# untitled.net
KiCad netlist of a schematic drawn in EAGLE
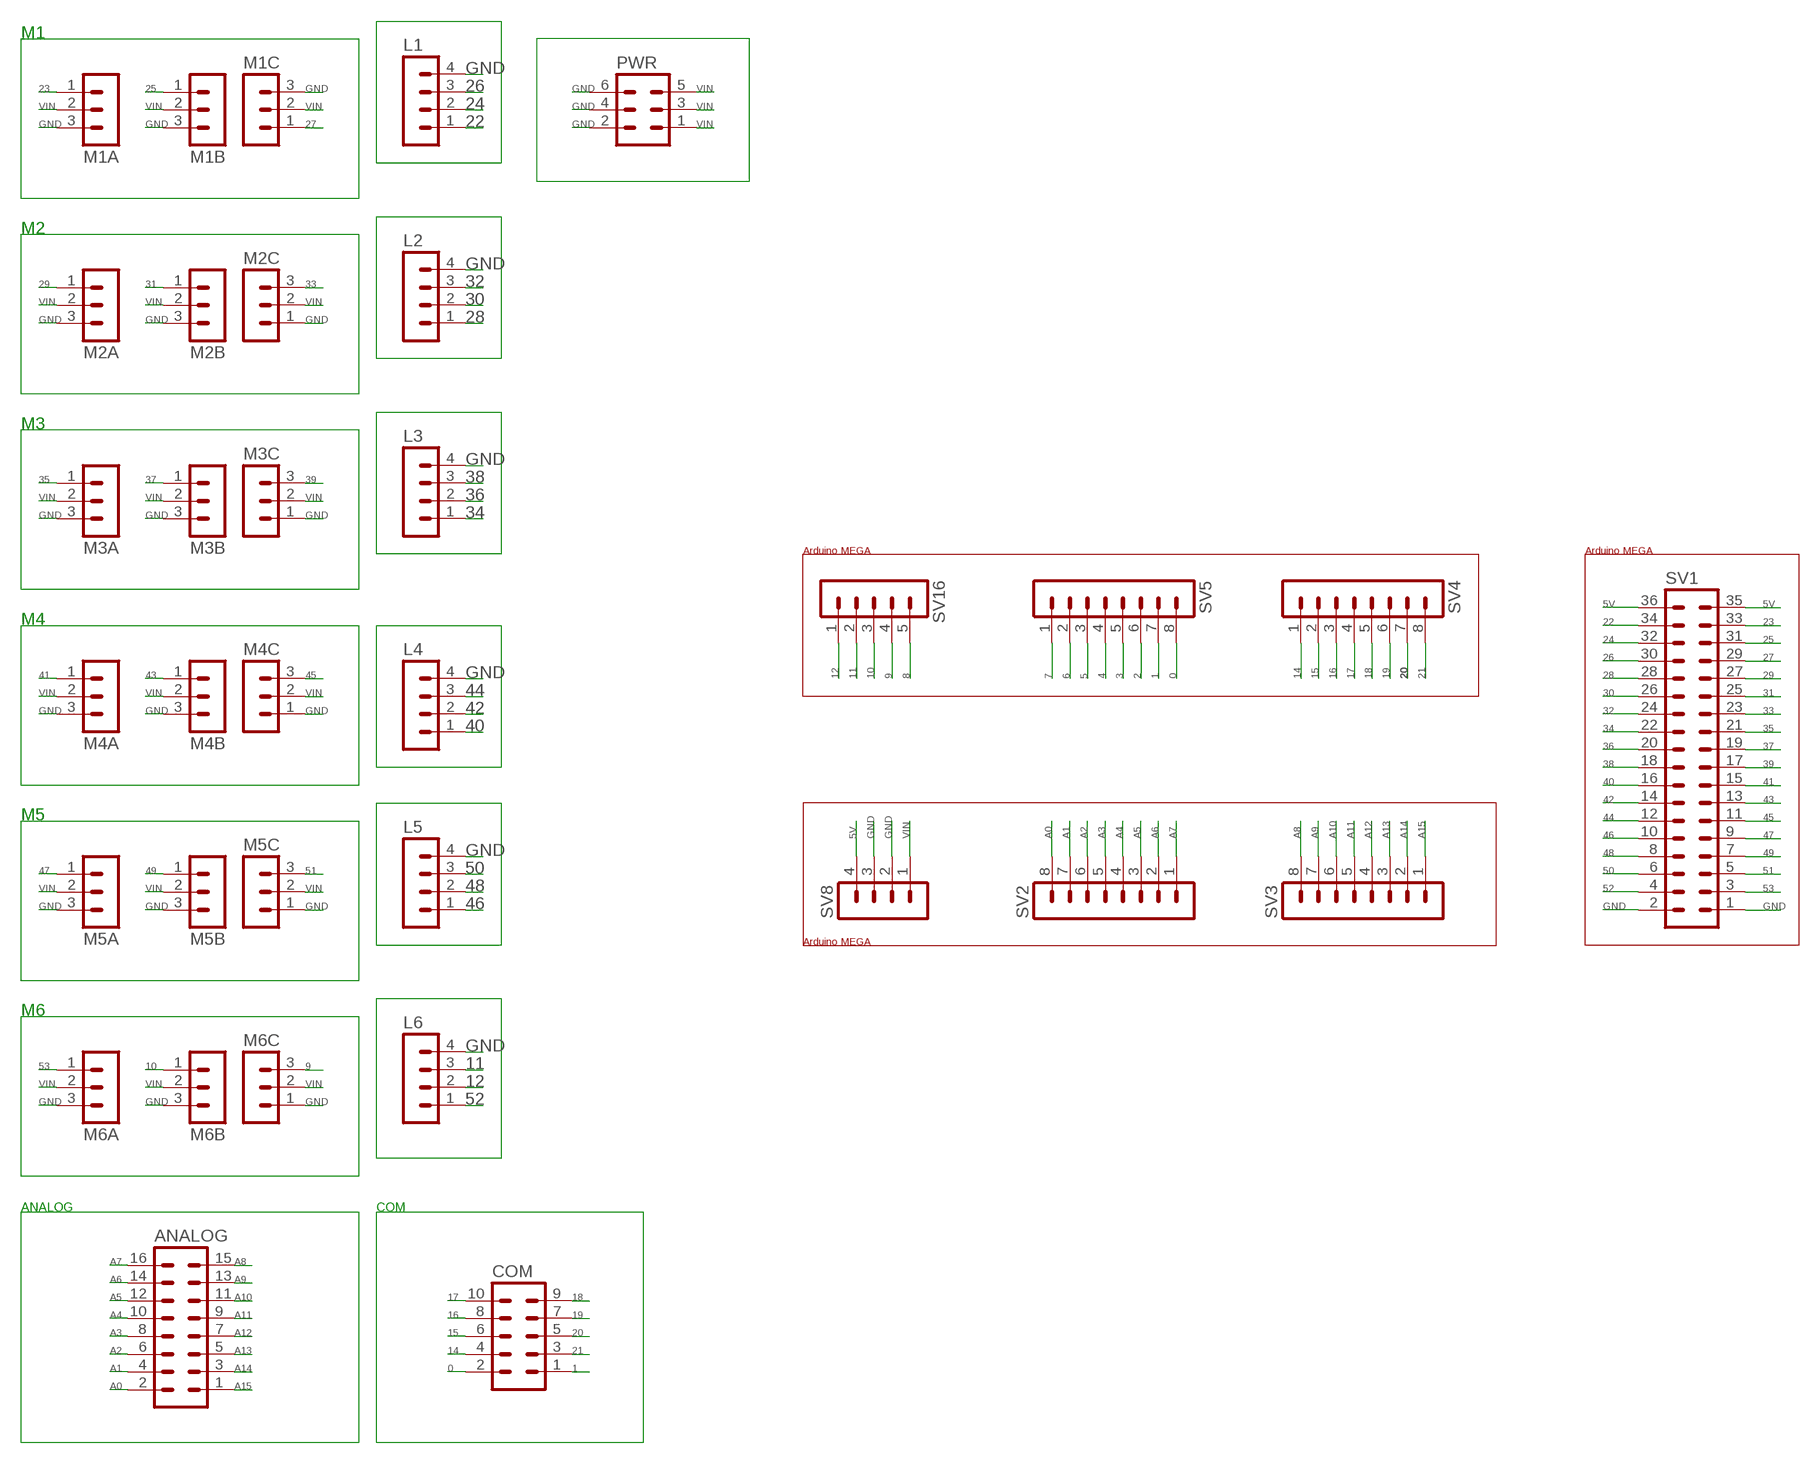
[diagram p0: schematic, sheet 1]

(export (version "E")
  (design (tool "Eeschema 10.0.6"))
  (components
    (comp (ref "ANALOG")
      (value "MA08-2")
      (footprint "eagle-import:MA08-2")
      (libsource (lib "eagle-import") (part "MA08-2"))
    )
    (comp (ref "COM")
      (value "MA05-2")
      (footprint "eagle-import:MA05-2")
      (libsource (lib "eagle-import") (part "MA05-2"))
    )
    (comp (ref "L1")
      (value "MA04-1")
      (footprint "eagle-import:MA04-1")
      (libsource (lib "eagle-import") (part "MA04-1"))
    )
    (comp (ref "L2")
      (value "MA04-1")
      (footprint "eagle-import:MA04-1")
      (libsource (lib "eagle-import") (part "MA04-1"))
    )
    (comp (ref "L3")
      (value "MA04-1")
      (footprint "eagle-import:MA04-1")
      (libsource (lib "eagle-import") (part "MA04-1"))
    )
    (comp (ref "L4")
      (value "MA04-1")
      (footprint "eagle-import:MA04-1")
      (libsource (lib "eagle-import") (part "MA04-1"))
    )
    (comp (ref "L5")
      (value "MA04-1")
      (footprint "eagle-import:MA04-1")
      (libsource (lib "eagle-import") (part "MA04-1"))
    )
    (comp (ref "L6")
      (value "MA04-1")
      (footprint "eagle-import:MA04-1")
      (libsource (lib "eagle-import") (part "MA04-1"))
    )
    (comp (ref "M1A")
      (value "MA03-1")
      (footprint "eagle-import:MA03-1")
      (libsource (lib "eagle-import") (part "MA03-1"))
    )
    (comp (ref "M1B")
      (value "MA03-1")
      (footprint "eagle-import:MA03-1")
      (libsource (lib "eagle-import") (part "MA03-1"))
    )
    (comp (ref "M1C")
      (value "MA03-1")
      (footprint "eagle-import:MA03-1")
      (libsource (lib "eagle-import") (part "MA03-1"))
    )
    (comp (ref "M2A")
      (value "MA03-1")
      (footprint "eagle-import:MA03-1")
      (libsource (lib "eagle-import") (part "MA03-1"))
    )
    (comp (ref "M2B")
      (value "MA03-1")
      (footprint "eagle-import:MA03-1")
      (libsource (lib "eagle-import") (part "MA03-1"))
    )
    (comp (ref "M2C")
      (value "MA03-1")
      (footprint "eagle-import:MA03-1")
      (libsource (lib "eagle-import") (part "MA03-1"))
    )
    (comp (ref "M3A")
      (value "MA03-1")
      (footprint "eagle-import:MA03-1")
      (libsource (lib "eagle-import") (part "MA03-1"))
    )
    (comp (ref "M3B")
      (value "MA03-1")
      (footprint "eagle-import:MA03-1")
      (libsource (lib "eagle-import") (part "MA03-1"))
    )
    (comp (ref "M3C")
      (value "MA03-1")
      (footprint "eagle-import:MA03-1")
      (libsource (lib "eagle-import") (part "MA03-1"))
    )
    (comp (ref "M4A")
      (value "MA03-1")
      (footprint "eagle-import:MA03-1")
      (libsource (lib "eagle-import") (part "MA03-1"))
    )
    (comp (ref "M4B")
      (value "MA03-1")
      (footprint "eagle-import:MA03-1")
      (libsource (lib "eagle-import") (part "MA03-1"))
    )
    (comp (ref "M4C")
      (value "MA03-1")
      (footprint "eagle-import:MA03-1")
      (libsource (lib "eagle-import") (part "MA03-1"))
    )
    (comp (ref "M5A")
      (value "MA03-1")
      (footprint "eagle-import:MA03-1")
      (libsource (lib "eagle-import") (part "MA03-1"))
    )
    (comp (ref "M5B")
      (value "MA03-1")
      (footprint "eagle-import:MA03-1")
      (libsource (lib "eagle-import") (part "MA03-1"))
    )
    (comp (ref "M5C")
      (value "MA03-1")
      (footprint "eagle-import:MA03-1")
      (libsource (lib "eagle-import") (part "MA03-1"))
    )
    (comp (ref "M6A")
      (value "MA03-1")
      (footprint "eagle-import:MA03-1")
      (libsource (lib "eagle-import") (part "MA03-1"))
    )
    (comp (ref "M6B")
      (value "MA03-1")
      (footprint "eagle-import:MA03-1")
      (libsource (lib "eagle-import") (part "MA03-1"))
    )
    (comp (ref "M6C")
      (value "MA03-1")
      (footprint "eagle-import:MA03-1")
      (libsource (lib "eagle-import") (part "MA03-1"))
    )
    (comp (ref "PWR")
      (value "MA03-2")
      (footprint "eagle-import:MA03-2")
      (libsource (lib "eagle-import") (part "MA03-2"))
    )
    (comp (ref "SV1")
      (value "MA18-2")
      (footprint "eagle-import:MA18-2")
      (libsource (lib "eagle-import") (part "MA18-2"))
    )
    (comp (ref "SV2")
      (value "MA08-1")
      (footprint "eagle-import:MA08-1")
      (libsource (lib "eagle-import") (part "MA08-1"))
    )
    (comp (ref "SV3")
      (value "MA08-1")
      (footprint "eagle-import:MA08-1")
      (libsource (lib "eagle-import") (part "MA08-1"))
    )
    (comp (ref "SV4")
      (value "MA08-1")
      (footprint "eagle-import:MA08-1")
      (libsource (lib "eagle-import") (part "MA08-1"))
    )
    (comp (ref "SV5")
      (value "MA08-1")
      (footprint "eagle-import:MA08-1")
      (libsource (lib "eagle-import") (part "MA08-1"))
    )
    (comp (ref "SV8")
      (value "MA04-1")
      (footprint "eagle-import:MA04-1")
      (libsource (lib "eagle-import") (part "MA04-1"))
    )
    (comp (ref "SV16")
      (value "MA05-1")
      (footprint "eagle-import:MA05-1")
      (libsource (lib "eagle-import") (part "MA05-1"))
    )
  )
  (nets
    (net (code "1") (name "/0") (class "Default")
      (node (ref "COM") (pin "2") (pinfunction "2_2") (pintype "passive"))
      (node (ref "SV5") (pin "8") (pinfunction "8_8") (pintype "passive"))
    )
    (net (code "2") (name "/1") (class "Default")
      (node (ref "COM") (pin "1") (pinfunction "1_1") (pintype "passive"))
      (node (ref "SV5") (pin "7") (pinfunction "7_7") (pintype "passive"))
    )
    (net (code "3") (name "/2") (class "Default")
      (node (ref "SV5") (pin "6") (pinfunction "6_6") (pintype "passive"))
    )
    (net (code "4") (name "/3") (class "Default")
      (node (ref "SV5") (pin "5") (pinfunction "5_5") (pintype "passive"))
    )
    (net (code "5") (name "/4") (class "Default")
      (node (ref "SV5") (pin "4") (pinfunction "4_4") (pintype "passive"))
    )
    (net (code "6") (name "/5") (class "Default")
      (node (ref "SV5") (pin "3") (pinfunction "3_3") (pintype "passive"))
    )
    (net (code "7") (name "/5V") (class "Default")
      (node (ref "SV1") (pin "35") (pinfunction "35_35") (pintype "passive"))
      (node (ref "SV1") (pin "36") (pinfunction "36_36") (pintype "passive"))
      (node (ref "SV8") (pin "4") (pinfunction "4_4") (pintype "passive"))
    )
    (net (code "8") (name "/6") (class "Default")
      (node (ref "SV5") (pin "2") (pinfunction "2_2") (pintype "passive"))
    )
    (net (code "9") (name "/7") (class "Default")
      (node (ref "SV5") (pin "1") (pinfunction "1_1") (pintype "passive"))
    )
    (net (code "10") (name "/8") (class "Default")
      (node (ref "SV16") (pin "5") (pinfunction "5_5") (pintype "passive"))
    )
    (net (code "11") (name "/9") (class "Default")
      (node (ref "M6C") (pin "3") (pinfunction "3_3") (pintype "passive"))
      (node (ref "SV16") (pin "4") (pinfunction "4_4") (pintype "passive"))
    )
    (net (code "12") (name "/10") (class "Default")
      (node (ref "M6B") (pin "1") (pinfunction "1_1") (pintype "passive"))
      (node (ref "SV16") (pin "3") (pinfunction "3_3") (pintype "passive"))
    )
    (net (code "13") (name "/11") (class "Default")
      (node (ref "L6") (pin "3") (pinfunction "3_3") (pintype "passive"))
      (node (ref "SV16") (pin "2") (pinfunction "2_2") (pintype "passive"))
    )
    (net (code "14") (name "/12") (class "Default")
      (node (ref "L6") (pin "2") (pinfunction "2_2") (pintype "passive"))
      (node (ref "SV16") (pin "1") (pinfunction "1_1") (pintype "passive"))
    )
    (net (code "15") (name "/14") (class "Default")
      (node (ref "COM") (pin "4") (pinfunction "4_4") (pintype "passive"))
      (node (ref "SV4") (pin "1") (pinfunction "1_1") (pintype "passive"))
    )
    (net (code "16") (name "/15") (class "Default")
      (node (ref "COM") (pin "6") (pinfunction "6_6") (pintype "passive"))
      (node (ref "SV4") (pin "2") (pinfunction "2_2") (pintype "passive"))
    )
    (net (code "17") (name "/16") (class "Default")
      (node (ref "COM") (pin "8") (pinfunction "8_8") (pintype "passive"))
      (node (ref "SV4") (pin "3") (pinfunction "3_3") (pintype "passive"))
    )
    (net (code "18") (name "/17") (class "Default")
      (node (ref "COM") (pin "10") (pinfunction "10_10") (pintype "passive"))
      (node (ref "SV4") (pin "4") (pinfunction "4_4") (pintype "passive"))
    )
    (net (code "19") (name "/18") (class "Default")
      (node (ref "COM") (pin "9") (pinfunction "9_9") (pintype "passive"))
      (node (ref "SV4") (pin "5") (pinfunction "5_5") (pintype "passive"))
    )
    (net (code "20") (name "/19") (class "Default")
      (node (ref "COM") (pin "7") (pinfunction "7_7") (pintype "passive"))
      (node (ref "SV4") (pin "6") (pinfunction "6_6") (pintype "passive"))
    )
    (net (code "21") (name "/20") (class "Default")
      (node (ref "COM") (pin "5") (pinfunction "5_5") (pintype "passive"))
      (node (ref "SV4") (pin "7") (pinfunction "7_7") (pintype "passive"))
    )
    (net (code "22") (name "/21") (class "Default")
      (node (ref "COM") (pin "3") (pinfunction "3_3") (pintype "passive"))
      (node (ref "SV4") (pin "8") (pinfunction "8_8") (pintype "passive"))
    )
    (net (code "23") (name "/22") (class "Default")
      (node (ref "L1") (pin "1") (pinfunction "1_1") (pintype "passive"))
      (node (ref "SV1") (pin "34") (pinfunction "34_34") (pintype "passive"))
    )
    (net (code "24") (name "/23") (class "Default")
      (node (ref "M1A") (pin "1") (pinfunction "1_1") (pintype "passive"))
      (node (ref "SV1") (pin "33") (pinfunction "33_33") (pintype "passive"))
    )
    (net (code "25") (name "/24") (class "Default")
      (node (ref "L1") (pin "2") (pinfunction "2_2") (pintype "passive"))
      (node (ref "SV1") (pin "32") (pinfunction "32_32") (pintype "passive"))
    )
    (net (code "26") (name "/25") (class "Default")
      (node (ref "M1B") (pin "1") (pinfunction "1_1") (pintype "passive"))
      (node (ref "SV1") (pin "31") (pinfunction "31_31") (pintype "passive"))
    )
    (net (code "27") (name "/26") (class "Default")
      (node (ref "L1") (pin "3") (pinfunction "3_3") (pintype "passive"))
      (node (ref "SV1") (pin "30") (pinfunction "30_30") (pintype "passive"))
    )
    (net (code "28") (name "/27") (class "Default")
      (node (ref "M1C") (pin "1") (pinfunction "1_1") (pintype "passive"))
      (node (ref "SV1") (pin "29") (pinfunction "29_29") (pintype "passive"))
    )
    (net (code "29") (name "/28") (class "Default")
      (node (ref "L2") (pin "1") (pinfunction "1_1") (pintype "passive"))
      (node (ref "SV1") (pin "28") (pinfunction "28_28") (pintype "passive"))
    )
    (net (code "30") (name "/29") (class "Default")
      (node (ref "M2A") (pin "1") (pinfunction "1_1") (pintype "passive"))
      (node (ref "SV1") (pin "27") (pinfunction "27_27") (pintype "passive"))
    )
    (net (code "31") (name "/30") (class "Default")
      (node (ref "L2") (pin "2") (pinfunction "2_2") (pintype "passive"))
      (node (ref "SV1") (pin "26") (pinfunction "26_26") (pintype "passive"))
    )
    (net (code "32") (name "/31") (class "Default")
      (node (ref "M2B") (pin "1") (pinfunction "1_1") (pintype "passive"))
      (node (ref "SV1") (pin "25") (pinfunction "25_25") (pintype "passive"))
    )
    (net (code "33") (name "/32") (class "Default")
      (node (ref "L2") (pin "3") (pinfunction "3_3") (pintype "passive"))
      (node (ref "SV1") (pin "24") (pinfunction "24_24") (pintype "passive"))
    )
    (net (code "34") (name "/33") (class "Default")
      (node (ref "M2C") (pin "3") (pinfunction "3_3") (pintype "passive"))
      (node (ref "SV1") (pin "23") (pinfunction "23_23") (pintype "passive"))
    )
    (net (code "35") (name "/34") (class "Default")
      (node (ref "L3") (pin "1") (pinfunction "1_1") (pintype "passive"))
      (node (ref "SV1") (pin "22") (pinfunction "22_22") (pintype "passive"))
    )
    (net (code "36") (name "/35") (class "Default")
      (node (ref "M3A") (pin "1") (pinfunction "1_1") (pintype "passive"))
      (node (ref "SV1") (pin "21") (pinfunction "21_21") (pintype "passive"))
    )
    (net (code "37") (name "/36") (class "Default")
      (node (ref "L3") (pin "2") (pinfunction "2_2") (pintype "passive"))
      (node (ref "SV1") (pin "20") (pinfunction "20_20") (pintype "passive"))
    )
    (net (code "38") (name "/37") (class "Default")
      (node (ref "M3B") (pin "1") (pinfunction "1_1") (pintype "passive"))
      (node (ref "SV1") (pin "19") (pinfunction "19_19") (pintype "passive"))
    )
    (net (code "39") (name "/38") (class "Default")
      (node (ref "L3") (pin "3") (pinfunction "3_3") (pintype "passive"))
      (node (ref "SV1") (pin "18") (pinfunction "18_18") (pintype "passive"))
    )
    (net (code "40") (name "/39") (class "Default")
      (node (ref "M3C") (pin "3") (pinfunction "3_3") (pintype "passive"))
      (node (ref "SV1") (pin "17") (pinfunction "17_17") (pintype "passive"))
    )
    (net (code "41") (name "/40") (class "Default")
      (node (ref "L4") (pin "1") (pinfunction "1_1") (pintype "passive"))
      (node (ref "SV1") (pin "16") (pinfunction "16_16") (pintype "passive"))
    )
    (net (code "42") (name "/41") (class "Default")
      (node (ref "M4A") (pin "1") (pinfunction "1_1") (pintype "passive"))
      (node (ref "SV1") (pin "15") (pinfunction "15_15") (pintype "passive"))
    )
    (net (code "43") (name "/42") (class "Default")
      (node (ref "L4") (pin "2") (pinfunction "2_2") (pintype "passive"))
      (node (ref "SV1") (pin "14") (pinfunction "14_14") (pintype "passive"))
    )
    (net (code "44") (name "/43") (class "Default")
      (node (ref "M4B") (pin "1") (pinfunction "1_1") (pintype "passive"))
      (node (ref "SV1") (pin "13") (pinfunction "13_13") (pintype "passive"))
    )
    (net (code "45") (name "/44") (class "Default")
      (node (ref "L4") (pin "3") (pinfunction "3_3") (pintype "passive"))
      (node (ref "SV1") (pin "12") (pinfunction "12_12") (pintype "passive"))
    )
    (net (code "46") (name "/45") (class "Default")
      (node (ref "M4C") (pin "3") (pinfunction "3_3") (pintype "passive"))
      (node (ref "SV1") (pin "11") (pinfunction "11_11") (pintype "passive"))
    )
    (net (code "47") (name "/46") (class "Default")
      (node (ref "L5") (pin "1") (pinfunction "1_1") (pintype "passive"))
      (node (ref "SV1") (pin "10") (pinfunction "10_10") (pintype "passive"))
    )
    (net (code "48") (name "/47") (class "Default")
      (node (ref "M5A") (pin "1") (pinfunction "1_1") (pintype "passive"))
      (node (ref "SV1") (pin "9") (pinfunction "9_9") (pintype "passive"))
    )
    (net (code "49") (name "/48") (class "Default")
      (node (ref "L5") (pin "2") (pinfunction "2_2") (pintype "passive"))
      (node (ref "SV1") (pin "8") (pinfunction "8_8") (pintype "passive"))
    )
    (net (code "50") (name "/49") (class "Default")
      (node (ref "M5B") (pin "1") (pinfunction "1_1") (pintype "passive"))
      (node (ref "SV1") (pin "7") (pinfunction "7_7") (pintype "passive"))
    )
    (net (code "51") (name "/50") (class "Default")
      (node (ref "L5") (pin "3") (pinfunction "3_3") (pintype "passive"))
      (node (ref "SV1") (pin "6") (pinfunction "6_6") (pintype "passive"))
    )
    (net (code "52") (name "/51") (class "Default")
      (node (ref "M5C") (pin "3") (pinfunction "3_3") (pintype "passive"))
      (node (ref "SV1") (pin "5") (pinfunction "5_5") (pintype "passive"))
    )
    (net (code "53") (name "/52") (class "Default")
      (node (ref "L6") (pin "1") (pinfunction "1_1") (pintype "passive"))
      (node (ref "SV1") (pin "4") (pinfunction "4_4") (pintype "passive"))
    )
    (net (code "54") (name "/53") (class "Default")
      (node (ref "M6A") (pin "1") (pinfunction "1_1") (pintype "passive"))
      (node (ref "SV1") (pin "3") (pinfunction "3_3") (pintype "passive"))
    )
    (net (code "55") (name "/A0") (class "Default")
      (node (ref "ANALOG") (pin "2") (pinfunction "2_2") (pintype "passive"))
      (node (ref "SV2") (pin "8") (pinfunction "8_8") (pintype "passive"))
    )
    (net (code "56") (name "/A1") (class "Default")
      (node (ref "ANALOG") (pin "4") (pinfunction "4_4") (pintype "passive"))
      (node (ref "SV2") (pin "7") (pinfunction "7_7") (pintype "passive"))
    )
    (net (code "57") (name "/A2") (class "Default")
      (node (ref "ANALOG") (pin "6") (pinfunction "6_6") (pintype "passive"))
      (node (ref "SV2") (pin "6") (pinfunction "6_6") (pintype "passive"))
    )
    (net (code "58") (name "/A3") (class "Default")
      (node (ref "ANALOG") (pin "8") (pinfunction "8_8") (pintype "passive"))
      (node (ref "SV2") (pin "5") (pinfunction "5_5") (pintype "passive"))
    )
    (net (code "59") (name "/A4") (class "Default")
      (node (ref "ANALOG") (pin "10") (pinfunction "10_10") (pintype "passive"))
      (node (ref "SV2") (pin "4") (pinfunction "4_4") (pintype "passive"))
    )
    (net (code "60") (name "/A5") (class "Default")
      (node (ref "ANALOG") (pin "12") (pinfunction "12_12") (pintype "passive"))
      (node (ref "SV2") (pin "3") (pinfunction "3_3") (pintype "passive"))
    )
    (net (code "61") (name "/A6") (class "Default")
      (node (ref "ANALOG") (pin "14") (pinfunction "14_14") (pintype "passive"))
      (node (ref "SV2") (pin "2") (pinfunction "2_2") (pintype "passive"))
    )
    (net (code "62") (name "/A7") (class "Default")
      (node (ref "ANALOG") (pin "16") (pinfunction "16_16") (pintype "passive"))
      (node (ref "SV2") (pin "1") (pinfunction "1_1") (pintype "passive"))
    )
    (net (code "63") (name "/A8") (class "Default")
      (node (ref "ANALOG") (pin "15") (pinfunction "15_15") (pintype "passive"))
      (node (ref "SV3") (pin "8") (pinfunction "8_8") (pintype "passive"))
    )
    (net (code "64") (name "/A9") (class "Default")
      (node (ref "ANALOG") (pin "13") (pinfunction "13_13") (pintype "passive"))
      (node (ref "SV3") (pin "7") (pinfunction "7_7") (pintype "passive"))
    )
    (net (code "65") (name "/A10") (class "Default")
      (node (ref "ANALOG") (pin "11") (pinfunction "11_11") (pintype "passive"))
      (node (ref "SV3") (pin "6") (pinfunction "6_6") (pintype "passive"))
    )
    (net (code "66") (name "/A11") (class "Default")
      (node (ref "ANALOG") (pin "9") (pinfunction "9_9") (pintype "passive"))
      (node (ref "SV3") (pin "5") (pinfunction "5_5") (pintype "passive"))
    )
    (net (code "67") (name "/A12") (class "Default")
      (node (ref "ANALOG") (pin "7") (pinfunction "7_7") (pintype "passive"))
      (node (ref "SV3") (pin "4") (pinfunction "4_4") (pintype "passive"))
    )
    (net (code "68") (name "/A13") (class "Default")
      (node (ref "ANALOG") (pin "5") (pinfunction "5_5") (pintype "passive"))
      (node (ref "SV3") (pin "3") (pinfunction "3_3") (pintype "passive"))
    )
    (net (code "69") (name "/A14") (class "Default")
      (node (ref "ANALOG") (pin "3") (pinfunction "3_3") (pintype "passive"))
      (node (ref "SV3") (pin "2") (pinfunction "2_2") (pintype "passive"))
    )
    (net (code "70") (name "/A15") (class "Default")
      (node (ref "ANALOG") (pin "1") (pinfunction "1_1") (pintype "passive"))
      (node (ref "SV3") (pin "1") (pinfunction "1_1") (pintype "passive"))
    )
    (net (code "71") (name "/GND") (class "Default")
      (node (ref "L1") (pin "4") (pinfunction "4_4") (pintype "passive"))
      (node (ref "L2") (pin "4") (pinfunction "4_4") (pintype "passive"))
      (node (ref "L3") (pin "4") (pinfunction "4_4") (pintype "passive"))
      (node (ref "L4") (pin "4") (pinfunction "4_4") (pintype "passive"))
      (node (ref "L5") (pin "4") (pinfunction "4_4") (pintype "passive"))
      (node (ref "L6") (pin "4") (pinfunction "4_4") (pintype "passive"))
      (node (ref "M1A") (pin "3") (pinfunction "3_3") (pintype "passive"))
      (node (ref "M1B") (pin "3") (pinfunction "3_3") (pintype "passive"))
      (node (ref "M1C") (pin "3") (pinfunction "3_3") (pintype "passive"))
      (node (ref "M2A") (pin "3") (pinfunction "3_3") (pintype "passive"))
      (node (ref "M2B") (pin "3") (pinfunction "3_3") (pintype "passive"))
      (node (ref "M2C") (pin "1") (pinfunction "1_1") (pintype "passive"))
      (node (ref "M3A") (pin "3") (pinfunction "3_3") (pintype "passive"))
      (node (ref "M3B") (pin "3") (pinfunction "3_3") (pintype "passive"))
      (node (ref "M3C") (pin "1") (pinfunction "1_1") (pintype "passive"))
      (node (ref "M4A") (pin "3") (pinfunction "3_3") (pintype "passive"))
      (node (ref "M4B") (pin "3") (pinfunction "3_3") (pintype "passive"))
      (node (ref "M4C") (pin "1") (pinfunction "1_1") (pintype "passive"))
      (node (ref "M5A") (pin "3") (pinfunction "3_3") (pintype "passive"))
      (node (ref "M5B") (pin "3") (pinfunction "3_3") (pintype "passive"))
      (node (ref "M5C") (pin "1") (pinfunction "1_1") (pintype "passive"))
      (node (ref "M6A") (pin "3") (pinfunction "3_3") (pintype "passive"))
      (node (ref "M6B") (pin "3") (pinfunction "3_3") (pintype "passive"))
      (node (ref "M6C") (pin "1") (pinfunction "1_1") (pintype "passive"))
      (node (ref "PWR") (pin "2") (pinfunction "2_2") (pintype "passive"))
      (node (ref "PWR") (pin "4") (pinfunction "4_4") (pintype "passive"))
      (node (ref "PWR") (pin "6") (pinfunction "6_6") (pintype "passive"))
      (node (ref "SV1") (pin "1") (pinfunction "1_1") (pintype "passive"))
      (node (ref "SV1") (pin "2") (pinfunction "2_2") (pintype "passive"))
      (node (ref "SV8") (pin "2") (pinfunction "2_2") (pintype "passive"))
      (node (ref "SV8") (pin "3") (pinfunction "3_3") (pintype "passive"))
    )
    (net (code "72") (name "/VIN") (class "Default")
      (node (ref "M1A") (pin "2") (pinfunction "2_2") (pintype "passive"))
      (node (ref "M1B") (pin "2") (pinfunction "2_2") (pintype "passive"))
      (node (ref "M1C") (pin "2") (pinfunction "2_2") (pintype "passive"))
      (node (ref "M2A") (pin "2") (pinfunction "2_2") (pintype "passive"))
      (node (ref "M2B") (pin "2") (pinfunction "2_2") (pintype "passive"))
      (node (ref "M2C") (pin "2") (pinfunction "2_2") (pintype "passive"))
      (node (ref "M3A") (pin "2") (pinfunction "2_2") (pintype "passive"))
      (node (ref "M3B") (pin "2") (pinfunction "2_2") (pintype "passive"))
      (node (ref "M3C") (pin "2") (pinfunction "2_2") (pintype "passive"))
      (node (ref "M4A") (pin "2") (pinfunction "2_2") (pintype "passive"))
      (node (ref "M4B") (pin "2") (pinfunction "2_2") (pintype "passive"))
      (node (ref "M4C") (pin "2") (pinfunction "2_2") (pintype "passive"))
      (node (ref "M5A") (pin "2") (pinfunction "2_2") (pintype "passive"))
      (node (ref "M5B") (pin "2") (pinfunction "2_2") (pintype "passive"))
      (node (ref "M5C") (pin "2") (pinfunction "2_2") (pintype "passive"))
      (node (ref "M6A") (pin "2") (pinfunction "2_2") (pintype "passive"))
      (node (ref "M6B") (pin "2") (pinfunction "2_2") (pintype "passive"))
      (node (ref "M6C") (pin "2") (pinfunction "2_2") (pintype "passive"))
      (node (ref "PWR") (pin "1") (pinfunction "1_1") (pintype "passive"))
      (node (ref "PWR") (pin "3") (pinfunction "3_3") (pintype "passive"))
      (node (ref "PWR") (pin "5") (pinfunction "5_5") (pintype "passive"))
      (node (ref "SV8") (pin "1") (pinfunction "1_1") (pintype "passive"))
    )
  )
)
